# 03-POWER.net
KiCad netlist of a schematic drawn in Altium Designer
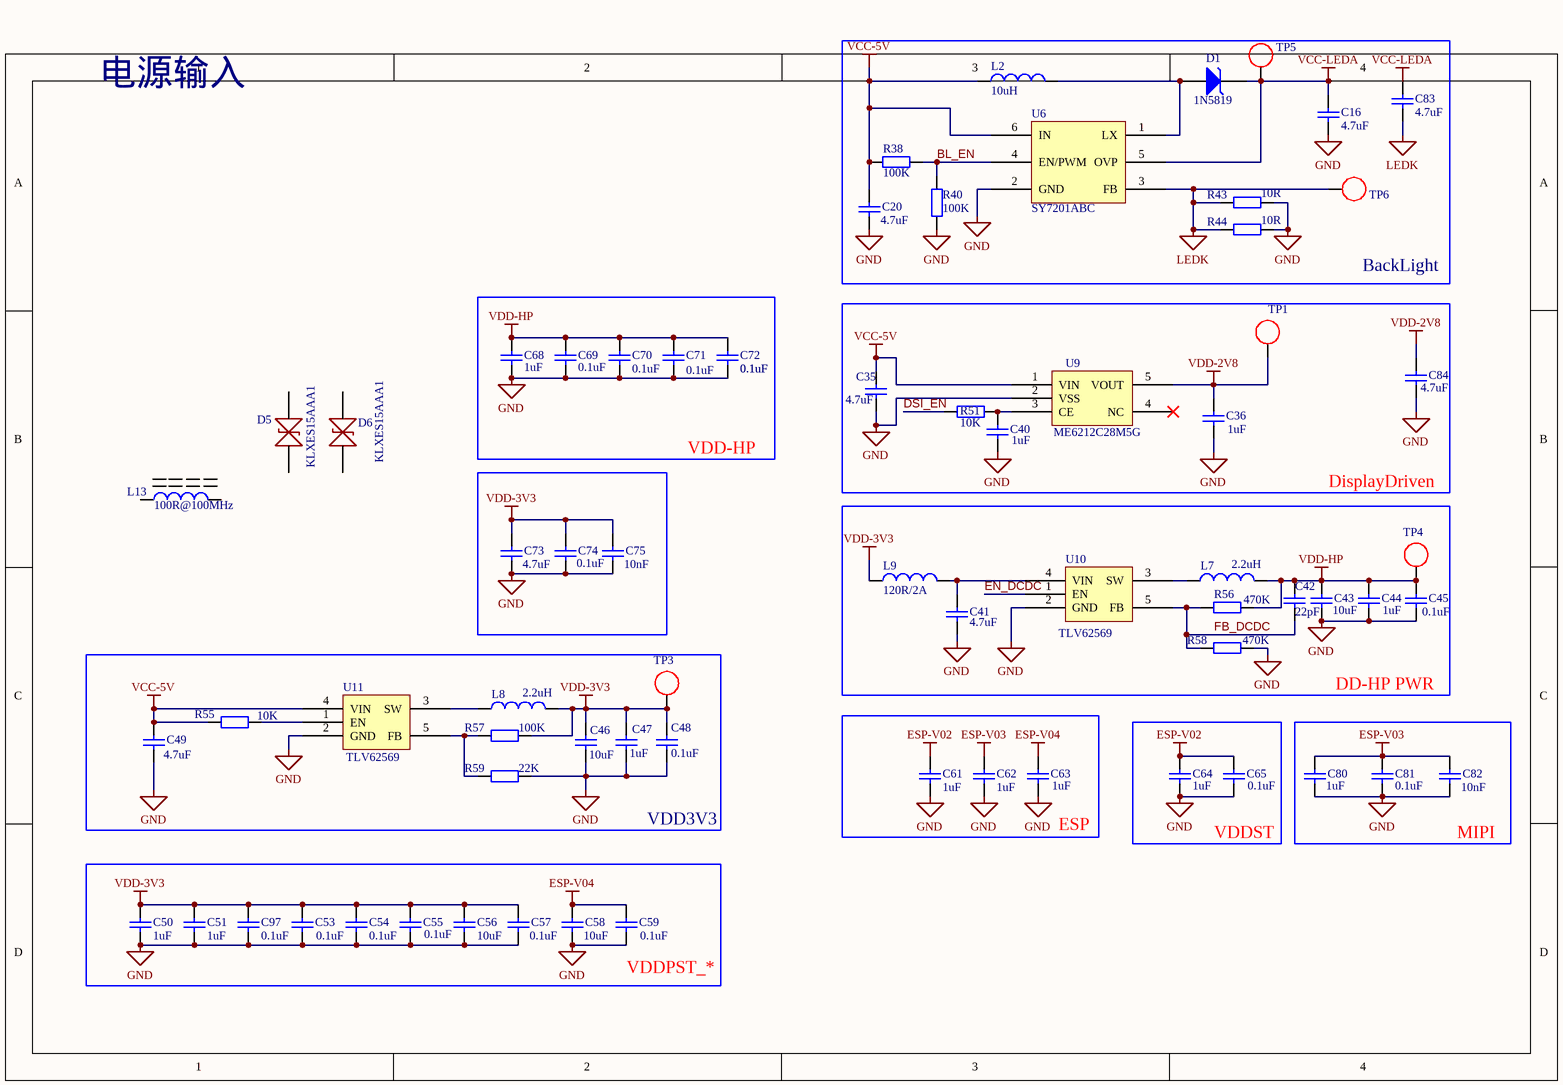
[diagram p0: 03-POWER.SchDoc]

(export (version "E")
  (design (tool "Eeschema 10.0.6"))
  (components
    (comp (ref "C16")
      (value "4.7uF")
      (footprint "C0603")
      (description "Capacitor")
      (libsource (lib "Simulation Generic Components") (part "Capacitor"))
    )
    (comp (ref "C20")
      (value "4.7uF")
      (footprint "C0603")
      (description "Capacitor")
      (libsource (lib "Simulation Generic Components") (part "Capacitor"))
    )
    (comp (ref "C35")
      (value "4.7uF")
      (footprint "C0603")
      (description "Capacitor")
      (libsource (lib "Simulation Generic Components") (part "Capacitor"))
    )
    (comp (ref "C36")
      (value "1uF")
      (footprint "C0402")
      (description "Capacitor")
      (libsource (lib "Simulation Generic Components") (part "Capacitor"))
    )
    (comp (ref "C40")
      (value "1uF")
      (footprint "C0402")
      (description "Capacitor")
      (libsource (lib "Simulation Generic Components") (part "Capacitor"))
    )
    (comp (ref "C41")
      (value "4.7uF")
      (footprint "C0603")
      (description "Capacitor")
      (libsource (lib "Simulation Generic Components") (part "Capacitor"))
    )
    (comp (ref "C42")
      (value "22pF")
      (footprint "C0402")
      (description "Capacitor")
      (libsource (lib "Simulation Generic Components") (part "Capacitor"))
    )
    (comp (ref "C43")
      (value "10uF")
      (footprint "C0805")
      (description "Capacitor")
      (libsource (lib "Simulation Generic Components") (part "Capacitor"))
    )
    (comp (ref "C44")
      (value "1uF")
      (footprint "C0402")
      (description "Capacitor")
      (libsource (lib "Simulation Generic Components") (part "Capacitor"))
    )
    (comp (ref "C45")
      (value "0.1uF")
      (footprint "C0402")
      (description "Capacitor")
      (libsource (lib "Simulation Generic Components") (part "Capacitor"))
    )
    (comp (ref "C46")
      (value "10uF")
      (footprint "C0805")
      (description "Capacitor")
      (libsource (lib "Simulation Generic Components") (part "Capacitor"))
    )
    (comp (ref "C47")
      (value "1uF")
      (footprint "C0402")
      (description "Capacitor")
      (libsource (lib "Simulation Generic Components") (part "Capacitor"))
    )
    (comp (ref "C48")
      (value "0.1uF")
      (footprint "C0402")
      (description "Capacitor")
      (libsource (lib "Simulation Generic Components") (part "Capacitor"))
    )
    (comp (ref "C49")
      (value "4.7uF")
      (footprint "C0603")
      (description "Capacitor")
      (libsource (lib "Simulation Generic Components") (part "Capacitor"))
    )
    (comp (ref "C50")
      (value "1uF")
      (footprint "C0402")
      (description "Capacitor")
      (libsource (lib "Simulation Generic Components") (part "Capacitor"))
    )
    (comp (ref "C51")
      (value "1uF")
      (footprint "C0402")
      (description "Capacitor")
      (libsource (lib "Simulation Generic Components") (part "Capacitor"))
    )
    (comp (ref "C53")
      (value "0.1uF")
      (footprint "C0402")
      (description "Capacitor")
      (libsource (lib "Simulation Generic Components") (part "Capacitor"))
    )
    (comp (ref "C54")
      (value "0.1uF")
      (footprint "C0402")
      (description "Capacitor")
      (libsource (lib "Simulation Generic Components") (part "Capacitor"))
    )
    (comp (ref "C55")
      (value "0.1uF")
      (footprint "C0402")
      (description "Capacitor")
      (libsource (lib "Simulation Generic Components") (part "Capacitor"))
    )
    (comp (ref "C56")
      (value "10uF")
      (footprint "C0805")
      (description "Capacitor")
      (libsource (lib "Simulation Generic Components") (part "Capacitor"))
    )
    (comp (ref "C57")
      (value "0.1uF")
      (footprint "C0402")
      (description "Capacitor")
      (libsource (lib "Simulation Generic Components") (part "Capacitor"))
    )
    (comp (ref "C58")
      (value "10uF")
      (footprint "C0805")
      (description "Capacitor")
      (libsource (lib "Simulation Generic Components") (part "Capacitor"))
    )
    (comp (ref "C59")
      (value "0.1uF")
      (footprint "C0402")
      (description "Capacitor")
      (libsource (lib "Simulation Generic Components") (part "Capacitor"))
    )
    (comp (ref "C61")
      (value "1uF")
      (footprint "C0402")
      (description "Capacitor")
      (libsource (lib "Simulation Generic Components") (part "Capacitor"))
    )
    (comp (ref "C62")
      (value "1uF")
      (footprint "C0402")
      (description "Capacitor")
      (libsource (lib "Simulation Generic Components") (part "Capacitor"))
    )
    (comp (ref "C63")
      (value "1uF")
      (footprint "C0402")
      (description "Capacitor")
      (libsource (lib "Simulation Generic Components") (part "Capacitor"))
    )
    (comp (ref "C64")
      (value "1uF")
      (footprint "C0402")
      (description "Capacitor")
      (libsource (lib "Simulation Generic Components") (part "Capacitor"))
    )
    (comp (ref "C65")
      (value "0.1uF")
      (footprint "C0402")
      (description "Capacitor")
      (libsource (lib "Simulation Generic Components") (part "Capacitor"))
    )
    (comp (ref "C68")
      (value "1uF")
      (footprint "C0402")
      (description "Capacitor")
      (libsource (lib "Simulation Generic Components") (part "Capacitor"))
    )
    (comp (ref "C69")
      (value "0.1uF")
      (footprint "C0402")
      (description "Capacitor")
      (libsource (lib "Simulation Generic Components") (part "Capacitor"))
    )
    (comp (ref "C70")
      (value "0.1uF")
      (footprint "C0402")
      (description "Capacitor")
      (libsource (lib "Simulation Generic Components") (part "Capacitor"))
    )
    (comp (ref "C71")
      (value "0.1uF")
      (footprint "C0402")
      (description "Capacitor")
      (libsource (lib "Simulation Generic Components") (part "Capacitor"))
    )
    (comp (ref "C72")
      (value "0.1uF")
      (footprint "C0402")
      (description "Capacitor")
      (fields (field (name "ALTIUM_VALUE") "0.1uF"))
      (libsource (lib "Simulation Generic Components") (part "Capacitor"))
    )
    (comp (ref "C73")
      (value "4.7uF")
      (footprint "C0603")
      (description "Capacitor")
      (libsource (lib "Simulation Generic Components") (part "Capacitor"))
    )
    (comp (ref "C74")
      (value "0.1uF")
      (footprint "C0402")
      (description "Capacitor")
      (libsource (lib "Simulation Generic Components") (part "Capacitor"))
    )
    (comp (ref "C75")
      (value "10nF")
      (footprint "C0402")
      (description "Capacitor")
      (libsource (lib "Simulation Generic Components") (part "Capacitor"))
    )
    (comp (ref "C80")
      (value "1uF")
      (footprint "C0402")
      (description "Capacitor")
      (libsource (lib "Simulation Generic Components") (part "Capacitor"))
    )
    (comp (ref "C81")
      (value "0.1uF")
      (footprint "C0402")
      (description "Capacitor")
      (libsource (lib "Simulation Generic Components") (part "Capacitor"))
    )
    (comp (ref "C82")
      (value "10nF")
      (footprint "C0402")
      (description "Capacitor")
      (libsource (lib "Simulation Generic Components") (part "Capacitor"))
    )
    (comp (ref "C83")
      (value "4.7uF")
      (footprint "C0603")
      (description "Capacitor")
      (libsource (lib "Simulation Generic Components") (part "Capacitor"))
    )
    (comp (ref "C84")
      (value "4.7uF")
      (footprint "C0603")
      (description "Capacitor")
      (libsource (lib "Simulation Generic Components") (part "Capacitor"))
    )
    (comp (ref "C97")
      (value "0.1uF")
      (footprint "C0402")
      (description "Capacitor")
      (libsource (lib "Simulation Generic Components") (part "Capacitor"))
    )
    (comp (ref "D1")
      (value "1N5819")
      (footprint "SOD-323_L1.8-W1.3-LS2.5-RD")
      (description "Suppressor Single")
      (libsource (lib "Simulation Generic Components") (part "Suppressor Single"))
    )
    (comp (ref "D5")
      (value "KLXES15AAA1")
      (footprint "D0402-BI")
      (libsource (lib "Schlib1") (part "KLXES15AAA1"))
    )
    (comp (ref "D6")
      (value "KLXES15AAA1")
      (footprint "D0402-BI")
      (libsource (lib "Schlib1") (part "KLXES15AAA1"))
    )
    (comp (ref "L2")
      (value "10uH")
      (footprint "L0603")
      (description "Inductor")
      (libsource (lib "Simulation Generic Components") (part "Inductor"))
    )
    (comp (ref "L7")
      (value "2.2uH")
      (footprint "IND-SMD_L2.5-W2.0_MHCHL2520")
      (description "Inductor")
      (libsource (lib "Simulation Generic Components") (part "Inductor"))
    )
    (comp (ref "L8")
      (value "2.2uH")
      (footprint "IND-SMD_L2.5-W2.0_MHCHL2520")
      (description "Inductor")
      (libsource (lib "Simulation Generic Components") (part "Inductor"))
    )
    (comp (ref "L9")
      (value "120R/2A")
      (footprint "L0603")
      (description "Inductor")
      (libsource (lib "Simulation Generic Components") (part "Inductor"))
    )
    (comp (ref "L13")
      (value "100R@100MHz")
      (footprint "LED0402-RD")
      (description "Inductor")
      (libsource (lib "PCB_Project") (part "Inductor"))
    )
    (comp (ref "R38")
      (value "100K")
      (footprint "R0402")
      (description "Resistor")
      (fields (field (name "PUBLISHER") "Altium Limited"))
      (libsource (lib "Miscellaneous Devices") (part "Res2"))
    )
    (comp (ref "R40")
      (value "100K")
      (footprint "R0402")
      (description "Resistor")
      (fields (field (name "PUBLISHER") "Altium Limited"))
      (libsource (lib "") (part "Res2_1"))
    )
    (comp (ref "R43")
      (value "10R")
      (footprint "R0805")
      (description "Resistor")
      (fields (field (name "PUBLISHER") "Altium Limited"))
      (libsource (lib "") (part "Res2_2"))
    )
    (comp (ref "R44")
      (value "10R")
      (footprint "R0805")
      (description "Resistor")
      (fields (field (name "PUBLISHER") "Altium Limited"))
      (libsource (lib "") (part "Res2_2"))
    )
    (comp (ref "R51")
      (value "10K")
      (footprint "R0402")
      (description "Resistor")
      (fields (field (name "PUBLISHER") "Altium Limited"))
      (libsource (lib "") (part "Res2_2"))
    )
    (comp (ref "R55")
      (value "10K")
      (footprint "R0402")
      (description "Resistor")
      (fields (field (name "PUBLISHER") "Altium Limited"))
      (libsource (lib "Miscellaneous Devices") (part "Res2"))
    )
    (comp (ref "R56")
      (value "470K")
      (footprint "R0402")
      (description "Resistor")
      (fields (field (name "PUBLISHER") "Altium Limited"))
      (libsource (lib "Miscellaneous Devices") (part "Res2"))
    )
    (comp (ref "R57")
      (value "100K")
      (footprint "R0402")
      (description "Resistor")
      (fields (field (name "PUBLISHER") "Altium Limited"))
      (libsource (lib "Miscellaneous Devices") (part "Res2"))
    )
    (comp (ref "R58")
      (value "470K")
      (footprint "R0402")
      (description "Resistor")
      (fields (field (name "PUBLISHER") "Altium Limited"))
      (libsource (lib "Miscellaneous Devices") (part "Res2"))
    )
    (comp (ref "R59")
      (value "22K")
      (footprint "R0402")
      (description "Resistor")
      (fields (field (name "PUBLISHER") "Altium Limited"))
      (libsource (lib "Miscellaneous Devices") (part "Res2"))
    )
    (comp (ref "TP1") (value "TP13") (footprint "Test-Point-1*1mm") (libsource (lib "Schlib1") (part "TP?")))
    (comp (ref "TP3") (value "TP13") (footprint "Test-Point-1*1mm") (libsource (lib "Schlib1") (part "TP?")))
    (comp (ref "TP4") (value "TP13") (footprint "Test-Point-1*1mm") (libsource (lib "Schlib1") (part "TP?")))
    (comp (ref "TP5") (value "TP13") (footprint "Test-Point-1*1mm") (libsource (lib "Schlib1") (part "TP?")))
    (comp (ref "TP6") (value "TP13") (footprint "Test-Point-1*1mm") (libsource (lib "Schlib1") (part "TP?")))
    (comp (ref "U6")
      (value "SY7201ABC")
      (footprint "SOT-23-6_L2.9-W1.6-P0.95-LS2.8-BL")
      (libsource (lib "Schlib1") (part "SY7201ABC"))
    )
    (comp (ref "U9")
      (value "ME6212C28M5G")
      (footprint "SOT-23-5_L3.0-W1.7-P0.95-LS2.8-BR")
      (libsource (lib "Schlib1") (part "ME6212C28M5G"))
    )
    (comp (ref "U10")
      (value "TLV62569")
      (footprint "SOT-23-5_L3.0-W1.7-P0.95-LS2.8-BR")
      (libsource (lib "Schlib1") (part "TLV62569"))
    )
    (comp (ref "U11")
      (value "TLV62569")
      (footprint "SOT-23-5_L3.0-W1.7-P0.95-LS2.8-BR")
      (libsource (lib "Schlib1") (part "TLV62569"))
    )
  )
  (nets
    (net (code "1") (name "/BL_EN") (class "Default")
      (node (ref "R38") (pin "2") (pinfunction "2_2") (pintype "passive"))
      (node (ref "R40") (pin "2") (pinfunction "2_2") (pintype "passive"))
      (node (ref "U6") (pin "4") (pinfunction "EN/PWM_4") (pintype "passive"))
    )
    (net (code "2") (name "/DSI_EN") (class "Default")
      (node (ref "R51") (pin "2") (pinfunction "2_2") (pintype "passive"))
    )
    (net (code "3") (name "/EN_DCDC") (class "Default")
      (node (ref "U10") (pin "1") (pinfunction "EN_1") (pintype "passive"))
    )
    (net (code "4") (name "/FB_DCDC") (class "Default")
      (node (ref "C42") (pin "2") (pinfunction "2_2") (pintype "passive"))
      (node (ref "R56") (pin "1") (pinfunction "1_1") (pintype "passive"))
      (node (ref "R58") (pin "1") (pinfunction "1_1") (pintype "passive"))
      (node (ref "U10") (pin "5") (pinfunction "FB_5") (pintype "passive"))
    )
    (net (code "5") (name "ESP-V02") (class "Default")
      (node (ref "C61") (pin "2") (pinfunction "2_2") (pintype "passive"))
      (node (ref "C64") (pin "2") (pinfunction "2_2") (pintype "passive"))
      (node (ref "C65") (pin "2") (pinfunction "2_2") (pintype "passive"))
    )
    (net (code "6") (name "ESP-V03") (class "Default")
      (node (ref "C62") (pin "2") (pinfunction "2_2") (pintype "passive"))
      (node (ref "C80") (pin "2") (pinfunction "2_2") (pintype "passive"))
      (node (ref "C81") (pin "2") (pinfunction "2_2") (pintype "passive"))
      (node (ref "C82") (pin "2") (pinfunction "2_2") (pintype "passive"))
    )
    (net (code "7") (name "ESP-V04") (class "Default")
      (node (ref "C58") (pin "2") (pinfunction "2_2") (pintype "passive"))
      (node (ref "C59") (pin "2") (pinfunction "2_2") (pintype "passive"))
      (node (ref "C63") (pin "2") (pinfunction "2_2") (pintype "passive"))
    )
    (net (code "8") (name "GND") (class "Default")
      (node (ref "C16") (pin "1") (pinfunction "1_1") (pintype "passive"))
      (node (ref "C20") (pin "1") (pinfunction "1_1") (pintype "passive"))
      (node (ref "C35") (pin "2") (pinfunction "2_2") (pintype "passive"))
      (node (ref "C36") (pin "2") (pinfunction "2_2") (pintype "passive"))
      (node (ref "C40") (pin "2") (pinfunction "2_2") (pintype "passive"))
      (node (ref "C41") (pin "2") (pinfunction "2_2") (pintype "passive"))
      (node (ref "C43") (pin "2") (pinfunction "2_2") (pintype "passive"))
      (node (ref "C44") (pin "2") (pinfunction "2_2") (pintype "passive"))
      (node (ref "C45") (pin "2") (pinfunction "2_2") (pintype "passive"))
      (node (ref "C46") (pin "2") (pinfunction "2_2") (pintype "passive"))
      (node (ref "C47") (pin "2") (pinfunction "2_2") (pintype "passive"))
      (node (ref "C48") (pin "2") (pinfunction "2_2") (pintype "passive"))
      (node (ref "C49") (pin "2") (pinfunction "2_2") (pintype "passive"))
      (node (ref "C50") (pin "1") (pinfunction "1_1") (pintype "passive"))
      (node (ref "C51") (pin "1") (pinfunction "1_1") (pintype "passive"))
      (node (ref "C53") (pin "1") (pinfunction "1_1") (pintype "passive"))
      (node (ref "C54") (pin "1") (pinfunction "1_1") (pintype "passive"))
      (node (ref "C55") (pin "1") (pinfunction "1_1") (pintype "passive"))
      (node (ref "C56") (pin "1") (pinfunction "1_1") (pintype "passive"))
      (node (ref "C57") (pin "1") (pinfunction "1_1") (pintype "passive"))
      (node (ref "C58") (pin "1") (pinfunction "1_1") (pintype "passive"))
      (node (ref "C59") (pin "1") (pinfunction "1_1") (pintype "passive"))
      (node (ref "C61") (pin "1") (pinfunction "1_1") (pintype "passive"))
      (node (ref "C62") (pin "1") (pinfunction "1_1") (pintype "passive"))
      (node (ref "C63") (pin "1") (pinfunction "1_1") (pintype "passive"))
      (node (ref "C64") (pin "1") (pinfunction "1_1") (pintype "passive"))
      (node (ref "C65") (pin "1") (pinfunction "1_1") (pintype "passive"))
      (node (ref "C68") (pin "1") (pinfunction "1_1") (pintype "passive"))
      (node (ref "C69") (pin "1") (pinfunction "1_1") (pintype "passive"))
      (node (ref "C70") (pin "1") (pinfunction "1_1") (pintype "passive"))
      (node (ref "C71") (pin "1") (pinfunction "1_1") (pintype "passive"))
      (node (ref "C72") (pin "1") (pinfunction "1_1") (pintype "passive"))
      (node (ref "C73") (pin "1") (pinfunction "1_1") (pintype "passive"))
      (node (ref "C74") (pin "1") (pinfunction "1_1") (pintype "passive"))
      (node (ref "C75") (pin "1") (pinfunction "1_1") (pintype "passive"))
      (node (ref "C80") (pin "1") (pinfunction "1_1") (pintype "passive"))
      (node (ref "C81") (pin "1") (pinfunction "1_1") (pintype "passive"))
      (node (ref "C82") (pin "1") (pinfunction "1_1") (pintype "passive"))
      (node (ref "C84") (pin "2") (pinfunction "2_2") (pintype "passive"))
      (node (ref "C97") (pin "1") (pinfunction "1_1") (pintype "passive"))
      (node (ref "R40") (pin "1") (pinfunction "1_1") (pintype "passive"))
      (node (ref "R43") (pin "1") (pinfunction "1_1") (pintype "passive"))
      (node (ref "R44") (pin "1") (pinfunction "1_1") (pintype "passive"))
      (node (ref "R58") (pin "2") (pinfunction "2_2") (pintype "passive"))
      (node (ref "R59") (pin "2") (pinfunction "2_2") (pintype "passive"))
      (node (ref "U10") (pin "2") (pinfunction "GND_2") (pintype "passive"))
      (node (ref "U11") (pin "2") (pinfunction "GND_2") (pintype "passive"))
      (node (ref "U6") (pin "2") (pinfunction "GND_2") (pintype "passive"))
      (node (ref "U9") (pin "2") (pinfunction "VSS_2") (pintype "passive"))
    )
    (net (code "9") (name "LEDK") (class "Default")
      (node (ref "C83") (pin "1") (pinfunction "1_1") (pintype "passive"))
      (node (ref "R43") (pin "2") (pinfunction "2_2") (pintype "passive"))
      (node (ref "R44") (pin "2") (pinfunction "2_2") (pintype "passive"))
      (node (ref "TP6") (pin "1") (pinfunction "1_1") (pintype "passive"))
      (node (ref "U6") (pin "3") (pinfunction "FB_3") (pintype "passive"))
    )
    (net (code "10") (name "Net-(D1-A)") (class "Default")
      (node (ref "D1") (pin "2") (pinfunction "A_2") (pintype "passive"))
      (node (ref "L2") (pin "2") (pinfunction "2_2") (pintype "passive"))
      (node (ref "U6") (pin "1") (pinfunction "LX_1") (pintype "passive"))
    )
    (net (code "11") (name "Net-(U9-CE)") (class "Default")
      (node (ref "C40") (pin "1") (pinfunction "1_1") (pintype "passive"))
      (node (ref "R51") (pin "1") (pinfunction "1_1") (pintype "passive"))
      (node (ref "U9") (pin "3") (pinfunction "CE_3") (pintype "passive"))
    )
    (net (code "12") (name "Net-(U10-SW)") (class "Default")
      (node (ref "L7") (pin "1") (pinfunction "1_1") (pintype "passive"))
      (node (ref "U10") (pin "3") (pinfunction "SW_3") (pintype "passive"))
    )
    (net (code "13") (name "Net-(U10-VIN)") (class "Default")
      (node (ref "C41") (pin "1") (pinfunction "1_1") (pintype "passive"))
      (node (ref "L9") (pin "2") (pinfunction "2_2") (pintype "passive"))
      (node (ref "U10") (pin "4") (pinfunction "VIN_4") (pintype "passive"))
    )
    (net (code "14") (name "Net-(U11-EN)") (class "Default")
      (node (ref "R55") (pin "2") (pinfunction "2_2") (pintype "passive"))
      (node (ref "U11") (pin "1") (pinfunction "EN_1") (pintype "passive"))
    )
    (net (code "15") (name "Net-(U11-FB)") (class "Default")
      (node (ref "R57") (pin "1") (pinfunction "1_1") (pintype "passive"))
      (node (ref "R59") (pin "1") (pinfunction "1_1") (pintype "passive"))
      (node (ref "U11") (pin "5") (pinfunction "FB_5") (pintype "passive"))
    )
    (net (code "16") (name "Net-(U11-SW)") (class "Default")
      (node (ref "L8") (pin "1") (pinfunction "1_1") (pintype "passive"))
      (node (ref "U11") (pin "3") (pinfunction "SW_3") (pintype "passive"))
    )
    (net (code "17") (name "VCC-5V") (class "Default")
      (node (ref "C20") (pin "2") (pinfunction "2_2") (pintype "passive"))
      (node (ref "C35") (pin "1") (pinfunction "1_1") (pintype "passive"))
      (node (ref "C49") (pin "1") (pinfunction "1_1") (pintype "passive"))
      (node (ref "L2") (pin "1") (pinfunction "1_1") (pintype "passive"))
      (node (ref "R38") (pin "1") (pinfunction "1_1") (pintype "passive"))
      (node (ref "R55") (pin "1") (pinfunction "1_1") (pintype "passive"))
      (node (ref "U11") (pin "4") (pinfunction "VIN_4") (pintype "passive"))
      (node (ref "U6") (pin "6") (pinfunction "IN_6") (pintype "passive"))
      (node (ref "U9") (pin "1") (pinfunction "VIN_1") (pintype "passive"))
    )
    (net (code "18") (name "VCC-LEDA") (class "Default")
      (node (ref "C16") (pin "2") (pinfunction "2_2") (pintype "passive"))
      (node (ref "C83") (pin "2") (pinfunction "2_2") (pintype "passive"))
      (node (ref "D1") (pin "1") (pinfunction "K_1") (pintype "passive"))
      (node (ref "TP5") (pin "1") (pinfunction "1_1") (pintype "passive"))
      (node (ref "U6") (pin "5") (pinfunction "OVP_5") (pintype "passive"))
    )
    (net (code "19") (name "VDD-2V8") (class "Default")
      (node (ref "C36") (pin "1") (pinfunction "1_1") (pintype "passive"))
      (node (ref "C84") (pin "1") (pinfunction "1_1") (pintype "passive"))
      (node (ref "TP1") (pin "1") (pinfunction "1_1") (pintype "passive"))
      (node (ref "U9") (pin "5") (pinfunction "VOUT_5") (pintype "passive"))
    )
    (net (code "20") (name "VDD-3V3") (class "Default")
      (node (ref "C46") (pin "1") (pinfunction "1_1") (pintype "passive"))
      (node (ref "C47") (pin "1") (pinfunction "1_1") (pintype "passive"))
      (node (ref "C48") (pin "1") (pinfunction "1_1") (pintype "passive"))
      (node (ref "C50") (pin "2") (pinfunction "2_2") (pintype "passive"))
      (node (ref "C51") (pin "2") (pinfunction "2_2") (pintype "passive"))
      (node (ref "C53") (pin "2") (pinfunction "2_2") (pintype "passive"))
      (node (ref "C54") (pin "2") (pinfunction "2_2") (pintype "passive"))
      (node (ref "C55") (pin "2") (pinfunction "2_2") (pintype "passive"))
      (node (ref "C56") (pin "2") (pinfunction "2_2") (pintype "passive"))
      (node (ref "C57") (pin "2") (pinfunction "2_2") (pintype "passive"))
      (node (ref "C73") (pin "2") (pinfunction "2_2") (pintype "passive"))
      (node (ref "C74") (pin "2") (pinfunction "2_2") (pintype "passive"))
      (node (ref "C75") (pin "2") (pinfunction "2_2") (pintype "passive"))
      (node (ref "C97") (pin "2") (pinfunction "2_2") (pintype "passive"))
      (node (ref "L8") (pin "2") (pinfunction "2_2") (pintype "passive"))
      (node (ref "L9") (pin "1") (pinfunction "1_1") (pintype "passive"))
      (node (ref "R57") (pin "2") (pinfunction "2_2") (pintype "passive"))
      (node (ref "TP3") (pin "1") (pinfunction "1_1") (pintype "passive"))
    )
    (net (code "21") (name "VDD-HP") (class "Default")
      (node (ref "C42") (pin "1") (pinfunction "1_1") (pintype "passive"))
      (node (ref "C43") (pin "1") (pinfunction "1_1") (pintype "passive"))
      (node (ref "C44") (pin "1") (pinfunction "1_1") (pintype "passive"))
      (node (ref "C45") (pin "1") (pinfunction "1_1") (pintype "passive"))
      (node (ref "C68") (pin "2") (pinfunction "2_2") (pintype "passive"))
      (node (ref "C69") (pin "2") (pinfunction "2_2") (pintype "passive"))
      (node (ref "C70") (pin "2") (pinfunction "2_2") (pintype "passive"))
      (node (ref "C71") (pin "2") (pinfunction "2_2") (pintype "passive"))
      (node (ref "C72") (pin "2") (pinfunction "2_2") (pintype "passive"))
      (node (ref "L7") (pin "2") (pinfunction "2_2") (pintype "passive"))
      (node (ref "R56") (pin "2") (pinfunction "2_2") (pintype "passive"))
      (node (ref "TP4") (pin "1") (pinfunction "1_1") (pintype "passive"))
    )
    (net (code "22") (name "unconnected-(D5-Pad1)") (class "Default")
      (node (ref "D5") (pin "1") (pinfunction "1_1") (pintype "passive"))
    )
    (net (code "23") (name "unconnected-(D5-Pad2)") (class "Default")
      (node (ref "D5") (pin "2") (pinfunction "2_2") (pintype "passive"))
    )
    (net (code "24") (name "unconnected-(D6-Pad1)") (class "Default")
      (node (ref "D6") (pin "1") (pinfunction "1_1") (pintype "passive"))
    )
    (net (code "25") (name "unconnected-(D6-Pad2)") (class "Default")
      (node (ref "D6") (pin "2") (pinfunction "2_2") (pintype "passive"))
    )
    (net (code "26") (name "unconnected-(L13-Pad1)") (class "Default")
      (node (ref "L13") (pin "1") (pinfunction "1_1") (pintype "passive"))
    )
    (net (code "27") (name "unconnected-(L13-Pad2)") (class "Default")
      (node (ref "L13") (pin "2") (pinfunction "2_2") (pintype "passive"))
    )
    (net (code "28") (name "unconnected-(U9-NC-Pad4)") (class "Default")
      (node (ref "U9") (pin "4") (pinfunction "NC_4") (pintype "passive+no_connect"))
    )
  )
)
